# design.net
KiCad netlist of a schematic drawn in Altium Designer
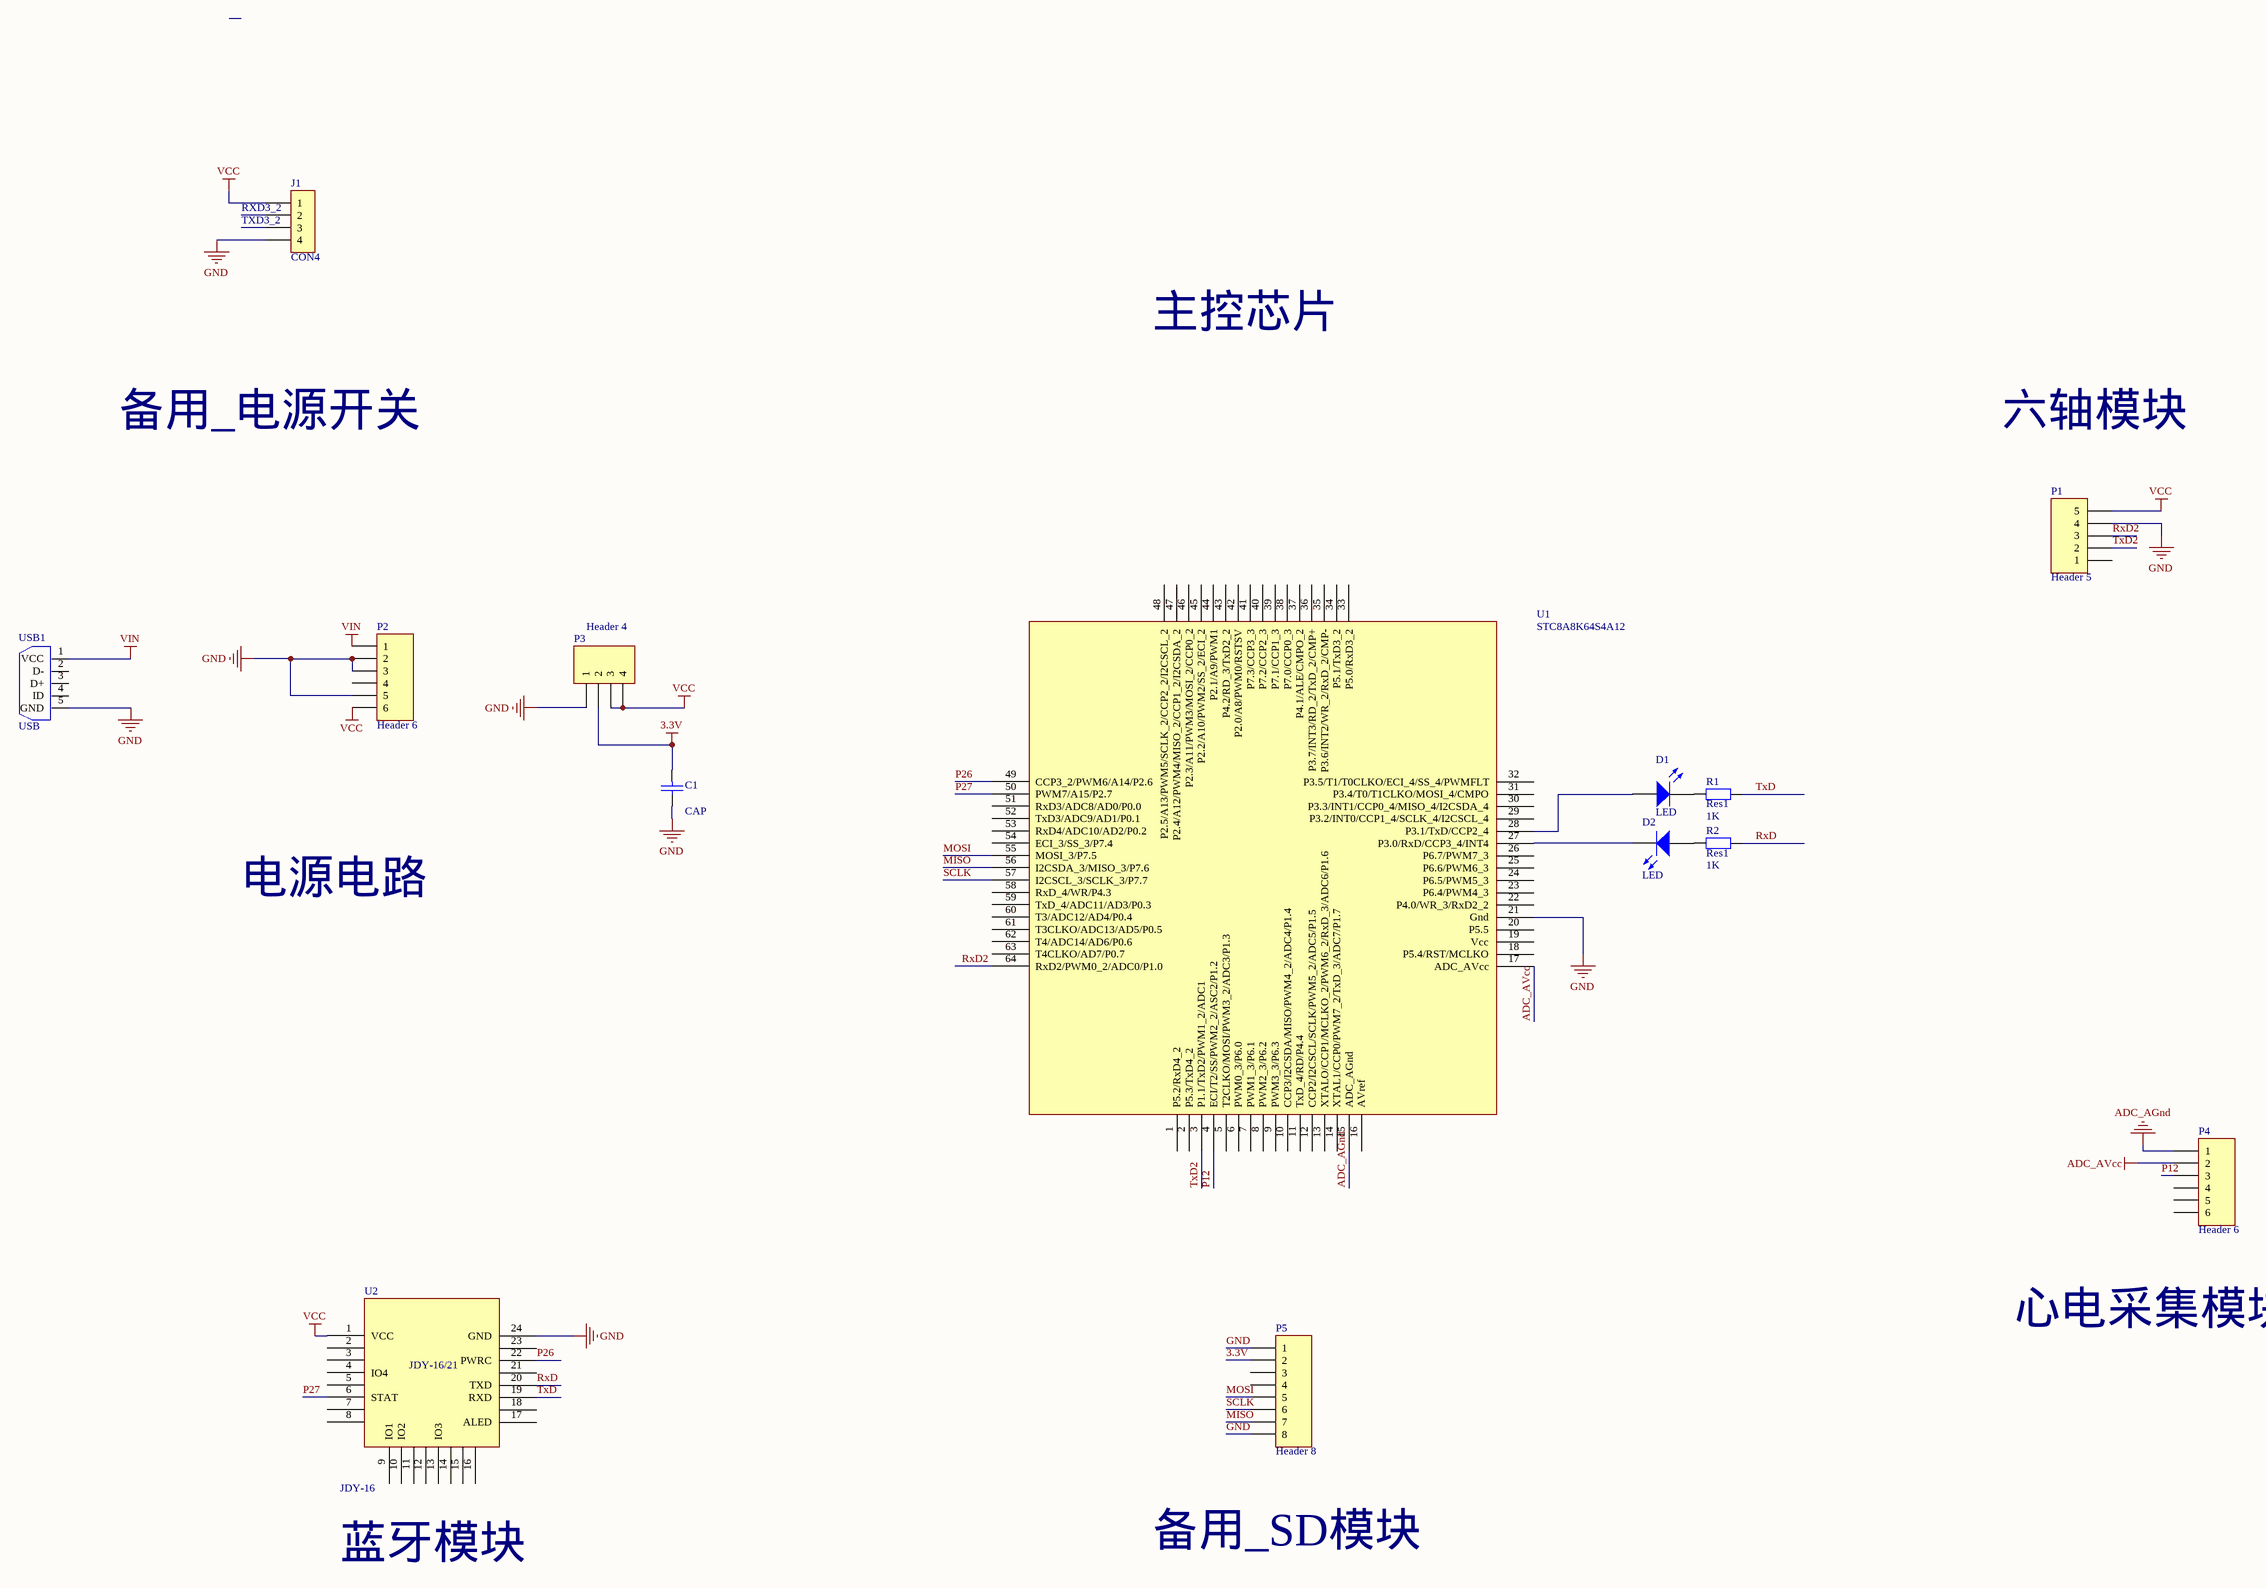
[diagram p0: 心电背心.SchDoc]

(export (version "E")
  (design (tool "Eeschema 10.0.6"))
  (components
    (comp (ref "C1")
      (value "CAP")
      (footprint "0805_L")
      (description "Capacitor")
      (libsource (lib "*") (part "CAP"))
    )
    (comp (ref "D1")
      (value "LED")
      (footprint "LED-0")
      (description "Typical INFRARED GaAs LED")
      (fields (field (name "PUBLISHER") "Altium Limited"))
      (libsource (lib "Miscellaneous Devices") (part "LED0"))
    )
    (comp (ref "D2")
      (value "LED")
      (footprint "LED-0")
      (description "Typical INFRARED GaAs LED")
      (fields (field (name "PUBLISHER") "Altium Limited"))
      (libsource (lib "Miscellaneous Devices") (part "LED0"))
    )
    (comp (ref "J1")
      (value "CON4")
      (footprint "SP4-1")
      (description "Connector")
      (libsource (lib "*") (part "CON4"))
    )
    (comp (ref "P1")
      (value "Header 5")
      (footprint "HDR1X5")
      (description "Header, 5-Pin")
      (fields (field (name "PUBLISHER") "Altium Limited"))
      (libsource (lib "Miscellaneous Connectors") (part "Header 5"))
    )
    (comp (ref "P2")
      (value "Header 6")
      (footprint "HT396K-6")
      (description "Header, 6-Pin")
      (fields (field (name "PUBLISHER") "Altium Limited"))
      (libsource (lib "01 Connect_IntegratedLibrary") (part "Header 6"))
    )
    (comp (ref "P3")
      (value "Header 4")
      (footprint "1117")
      (description "Header, 4-Pin")
      (fields (field (name "PUBLISHER") "Altium Limited"))
      (libsource (lib "Miscellaneous Connectors") (part "Header 4"))
    )
    (comp (ref "P4")
      (value "Header 6")
      (footprint "HT396K-6")
      (description "Header, 6-Pin")
      (fields (field (name "PUBLISHER") "Altium Limited"))
      (libsource (lib "01 Connect_IntegratedLibrary") (part "Header 6"))
    )
    (comp (ref "P5")
      (value "Header 8")
      (footprint "HDR1X8")
      (description "Header, 8-Pin")
      (fields (field (name "PUBLISHER") "Altium Limited"))
      (libsource (lib "03-EButterflyIntegratedLibrary") (part "Header 8"))
    )
    (comp (ref "R1")
      (value "Res1")
      (footprint "AXIAL-0.4")
      (description "Resistor")
      (fields (field (name "ALTIUM_VALUE") "1K") (field (name "PUBLISHER") "Altium Limited"))
      (libsource (lib "Miscellaneous Devices") (part "Res2"))
    )
    (comp (ref "R2")
      (value "Res1")
      (footprint "AXIAL-0.4")
      (description "Resistor")
      (fields (field (name "ALTIUM_VALUE") "1K") (field (name "PUBLISHER") "Altium Limited"))
      (libsource (lib "Miscellaneous Devices") (part "Res2"))
    )
    (comp (ref "U1")
      (value "STC8A8K64S4A12")
      (footprint "LQFP-64_10x10x05P_Q2")
      (description "LQFP64")
      (libsource (lib "02 Miscellaneous_Devices_ZSF_Library") (part "STC8A8K64S4A12"))
    )
    (comp (ref "U2") (value "JDY-16") (footprint "JDY16") (libsource (lib "stc64") (part "JDY21")))
    (comp (ref "USB1")
      (value "USB")
      (footprint "MICRO_USB5P_SOP")
      (libsource (lib "01 Connect_IntegratedLibrary") (part "USB5"))
    )
  )
  (nets
    (net (code "1") (name "/MISO") (class "Default")
      (node (ref "P5") (pin "7") (pinfunction "7_7") (pintype "passive"))
      (node (ref "U1") (pin "56") (pinfunction "I2CSDA_3/MISO_3/P7.6_56") (pintype "passive"))
    )
    (net (code "2") (name "/MOSI") (class "Default")
      (node (ref "P5") (pin "5") (pinfunction "5_5") (pintype "passive"))
      (node (ref "U1") (pin "55") (pinfunction "MOSI_3/P7.5_55") (pintype "passive"))
    )
    (net (code "3") (name "/P12") (class "Default")
      (node (ref "P4") (pin "3") (pinfunction "3_3") (pintype "passive"))
      (node (ref "U1") (pin "4") (pinfunction "ECI/T2/SS/PWM2_2/ASC2/P1.2_4") (pintype "passive"))
    )
    (net (code "4") (name "/P26") (class "Default")
      (node (ref "U1") (pin "49") (pinfunction "CCP3_2/PWM6/A14/P2.6_49") (pintype "passive"))
      (node (ref "U2") (pin "22") (pinfunction "PWRC_22") (pintype "passive"))
    )
    (net (code "5") (name "/P27") (class "Default")
      (node (ref "U1") (pin "50") (pinfunction "PWM7/A15/P2.7_50") (pintype "passive"))
      (node (ref "U2") (pin "6") (pinfunction "STAT_6") (pintype "passive"))
    )
    (net (code "6") (name "/RxD") (class "Default")
      (node (ref "R2") (pin "2") (pinfunction "2_2") (pintype "passive"))
      (node (ref "U2") (pin "20") (pinfunction "TXD_20") (pintype "passive"))
    )
    (net (code "7") (name "/RxD2") (class "Default")
      (node (ref "P1") (pin "3") (pinfunction "3_3") (pintype "passive"))
      (node (ref "U1") (pin "64") (pinfunction "RxD2/PWM0_2/ADC0/P1.0_64") (pintype "passive"))
    )
    (net (code "8") (name "/SCLK") (class "Default")
      (node (ref "P5") (pin "6") (pinfunction "6_6") (pintype "passive"))
      (node (ref "U1") (pin "57") (pinfunction "I2CSCL_3/SCLK_3/P7.7_57") (pintype "passive"))
    )
    (net (code "9") (name "/TxD") (class "Default")
      (node (ref "R1") (pin "2") (pinfunction "2_2") (pintype "passive"))
      (node (ref "U2") (pin "19") (pinfunction "RXD_19") (pintype "passive"))
    )
    (net (code "10") (name "/TxD2") (class "Default")
      (node (ref "P1") (pin "2") (pinfunction "2_2") (pintype "passive"))
      (node (ref "U1") (pin "3") (pinfunction "P1.1/TxD2/PWM1_2/ADC1_3") (pintype "passive"))
    )
    (net (code "11") (name "3.3V") (class "Default")
      (node (ref "C1") (pin "1") (pinfunction "1_1") (pintype "passive"))
      (node (ref "P3") (pin "2") (pinfunction "2_2") (pintype "passive"))
      (node (ref "P5") (pin "2") (pinfunction "2_2") (pintype "passive"))
    )
    (net (code "12") (name "ADC_AGnd") (class "Default")
      (node (ref "P4") (pin "1") (pinfunction "1_1") (pintype "passive"))
      (node (ref "U1") (pin "15") (pinfunction "ADC_AGnd_15") (pintype "passive"))
    )
    (net (code "13") (name "ADC_AVcc") (class "Default")
      (node (ref "P4") (pin "2") (pinfunction "2_2") (pintype "passive"))
      (node (ref "U1") (pin "17") (pinfunction "ADC_AVcc_17") (pintype "passive"))
    )
    (net (code "14") (name "GND") (class "Default")
      (node (ref "C1") (pin "2") (pinfunction "2_2") (pintype "passive"))
      (node (ref "J1") (pin "4") (pinfunction "4_4") (pintype "passive"))
      (node (ref "P1") (pin "4") (pinfunction "4_4") (pintype "passive"))
      (node (ref "P2") (pin "2") (pinfunction "2_2") (pintype "passive"))
      (node (ref "P2") (pin "3") (pinfunction "3_3") (pintype "passive"))
      (node (ref "P2") (pin "5") (pinfunction "5_5") (pintype "passive"))
      (node (ref "P3") (pin "1") (pinfunction "1_1") (pintype "passive"))
      (node (ref "P5") (pin "1") (pinfunction "1_1") (pintype "passive"))
      (node (ref "P5") (pin "8") (pinfunction "8_8") (pintype "passive"))
      (node (ref "U1") (pin "21") (pinfunction "Gnd_21") (pintype "passive"))
      (node (ref "U2") (pin "24") (pinfunction "GND_24") (pintype "passive"))
      (node (ref "USB1") (pin "5") (pinfunction "GND_5") (pintype "passive"))
    )
    (net (code "15") (name "Net-(D1-A)") (class "Default")
      (node (ref "D1") (pin "1") (pinfunction "A_1") (pintype "passive"))
      (node (ref "U1") (pin "28") (pinfunction "P3.1/TxD/CCP2_4_28") (pintype "passive"))
    )
    (net (code "16") (name "Net-(D1-K)") (class "Default")
      (node (ref "D1") (pin "2") (pinfunction "K_2") (pintype "passive"))
      (node (ref "R1") (pin "1") (pinfunction "1_1") (pintype "passive"))
    )
    (net (code "17") (name "Net-(D2-A)") (class "Default")
      (node (ref "D2") (pin "1") (pinfunction "A_1") (pintype "passive"))
      (node (ref "R2") (pin "1") (pinfunction "1_1") (pintype "passive"))
    )
    (net (code "18") (name "Net-(D2-K)") (class "Default")
      (node (ref "D2") (pin "2") (pinfunction "K_2") (pintype "passive"))
      (node (ref "U1") (pin "27") (pinfunction "P3.0/RxD/CCP3_4/INT4_27") (pintype "passive"))
    )
    (net (code "19") (name "VCC") (class "Default")
      (node (ref "J1") (pin "1") (pinfunction "1_1") (pintype "passive"))
      (node (ref "P1") (pin "5") (pinfunction "5_5") (pintype "passive"))
      (node (ref "P2") (pin "6") (pinfunction "6_6") (pintype "passive"))
      (node (ref "P3") (pin "3") (pinfunction "3_3") (pintype "passive"))
      (node (ref "P3") (pin "4") (pinfunction "4_4") (pintype "passive"))
      (node (ref "U2") (pin "1") (pinfunction "VCC_1") (pintype "passive"))
    )
    (net (code "20") (name "VIN") (class "Default")
      (node (ref "P2") (pin "1") (pinfunction "1_1") (pintype "passive"))
      (node (ref "USB1") (pin "1") (pinfunction "VCC_1") (pintype "passive"))
    )
    (net (code "21") (name "unconnected-(J1-Pad2)") (class "Default")
      (node (ref "J1") (pin "2") (pinfunction "2_2") (pintype "passive"))
    )
    (net (code "22") (name "unconnected-(J1-Pad3)") (class "Default")
      (node (ref "J1") (pin "3") (pinfunction "3_3") (pintype "passive"))
    )
    (net (code "23") (name "unconnected-(P1-Pad1)") (class "Default")
      (node (ref "P1") (pin "1") (pinfunction "1_1") (pintype "passive"))
    )
    (net (code "24") (name "unconnected-(P2-Pad4)") (class "Default")
      (node (ref "P2") (pin "4") (pinfunction "4_4") (pintype "passive"))
    )
    (net (code "25") (name "unconnected-(P4-Pad4)") (class "Default")
      (node (ref "P4") (pin "4") (pinfunction "4_4") (pintype "passive"))
    )
    (net (code "26") (name "unconnected-(P4-Pad5)") (class "Default")
      (node (ref "P4") (pin "5") (pinfunction "5_5") (pintype "passive"))
    )
    (net (code "27") (name "unconnected-(P4-Pad6)") (class "Default")
      (node (ref "P4") (pin "6") (pinfunction "6_6") (pintype "passive"))
    )
    (net (code "28") (name "unconnected-(P5-Pad3)") (class "Default")
      (node (ref "P5") (pin "3") (pinfunction "3_3") (pintype "passive"))
    )
    (net (code "29") (name "unconnected-(P5-Pad4)") (class "Default")
      (node (ref "P5") (pin "4") (pinfunction "4_4") (pintype "passive"))
    )
    (net (code "30") (name "unconnected-(U1-AVref-Pad16)") (class "Default")
      (node (ref "U1") (pin "16") (pinfunction "AVref_16") (pintype "passive"))
    )
    (net (code "31") (name "unconnected-(U1-CCP2{slash}I2CSCL{slash}SCLK{slash}PWM5_2{slash}ADC5{slash}P1.5-Pad12)") (class "Default")
      (node (ref "U1") (pin "12") (pinfunction "CCP2/I2CSCL/SCLK/PWM5_2/ADC5/P1.5_12") (pintype "passive"))
    )
    (net (code "32") (name "unconnected-(U1-CCP3{slash}I2CSDA{slash}MISO{slash}PWM4_2{slash}ADC4{slash}P1.4-Pad10)") (class "Default")
      (node (ref "U1") (pin "10") (pinfunction "CCP3/I2CSDA/MISO/PWM4_2/ADC4/P1.4_10") (pintype "passive"))
    )
    (net (code "33") (name "unconnected-(U1-ECI_3{slash}SS_3{slash}P7.4-Pad54)") (class "Default")
      (node (ref "U1") (pin "54") (pinfunction "ECI_3/SS_3/P7.4_54") (pintype "passive"))
    )
    (net (code "34") (name "unconnected-(U1-P2.0{slash}A8{slash}PWM0{slash}RSTSV-Pad42)") (class "Default")
      (node (ref "U1") (pin "42") (pinfunction "P2.0/A8/PWM0/RSTSV_42") (pintype "passive"))
    )
    (net (code "35") (name "unconnected-(U1-P2.1{slash}A9{slash}PWM1-Pad44)") (class "Default")
      (node (ref "U1") (pin "44") (pinfunction "P2.1/A9/PWM1_44") (pintype "passive"))
    )
    (net (code "36") (name "unconnected-(U1-P2.2{slash}A10{slash}PWM2{slash}SS_2{slash}ECI_2-Pad45)") (class "Default")
      (node (ref "U1") (pin "45") (pinfunction "P2.2/A10/PWM2/SS_2/ECI_2_45") (pintype "passive"))
    )
    (net (code "37") (name "unconnected-(U1-P2.3{slash}A11{slash}PWM3{slash}MOSI_2{slash}CCP0_2-Pad46)") (class "Default")
      (node (ref "U1") (pin "46") (pinfunction "P2.3/A11/PWM3/MOSI_2/CCP0_2_46") (pintype "passive"))
    )
    (net (code "38") (name "unconnected-(U1-P2.4{slash}A12{slash}PWM4{slash}MISO_2{slash}CCP1_2{slash}I2CSDA_2-Pad47)") (class "Default")
      (node (ref "U1") (pin "47") (pinfunction "P2.4/A12/PWM4/MISO_2/CCP1_2/I2CSDA_2_47") (pintype "passive"))
    )
    (net (code "39") (name "unconnected-(U1-P2.5{slash}A13{slash}PWM5{slash}SCLK_2{slash}CCP2_2{slash}I2CSCL_2-Pad48)") (class "Default")
      (node (ref "U1") (pin "48") (pinfunction "P2.5/A13/PWM5/SCLK_2/CCP2_2/I2CSCL_2_48") (pintype "passive"))
    )
    (net (code "40") (name "unconnected-(U1-P3.2{slash}INT0{slash}CCP1_4{slash}SCLK_4{slash}I2CSCL_4-Pad29)") (class "Default")
      (node (ref "U1") (pin "29") (pinfunction "P3.2/INT0/CCP1_4/SCLK_4/I2CSCL_4_29") (pintype "passive"))
    )
    (net (code "41") (name "unconnected-(U1-P3.3{slash}INT1{slash}CCP0_4{slash}MISO_4{slash}I2CSDA_4-Pad30)") (class "Default")
      (node (ref "U1") (pin "30") (pinfunction "P3.3/INT1/CCP0_4/MISO_4/I2CSDA_4_30") (pintype "passive"))
    )
    (net (code "42") (name "unconnected-(U1-P3.4{slash}T0{slash}T1CLKO{slash}MOSI_4{slash}CMPO-Pad31)") (class "Default")
      (node (ref "U1") (pin "31") (pinfunction "P3.4/T0/T1CLKO/MOSI_4/CMPO_31") (pintype "passive"))
    )
    (net (code "43") (name "unconnected-(U1-P3.5{slash}T1{slash}T0CLKO{slash}ECI_4{slash}SS_4{slash}PWMFLT-Pad32)") (class "Default")
      (node (ref "U1") (pin "32") (pinfunction "P3.5/T1/T0CLKO/ECI_4/SS_4/PWMFLT_32") (pintype "passive"))
    )
    (net (code "44") (name "unconnected-(U1-P3.6{slash}INT2{slash}WR_2{slash}RxD_2{slash}CMP--Pad35)") (class "Default")
      (node (ref "U1") (pin "35") (pinfunction "P3.6/INT2/WR_2/RxD_2/CMP-_35") (pintype "passive"))
    )
    (net (code "45") (name "unconnected-(U1-P3.7{slash}INT3{slash}RD_2{slash}TxD_2{slash}CMP+-Pad36)") (class "Default")
      (node (ref "U1") (pin "36") (pinfunction "P3.7/INT3/RD_2/TxD_2/CMP+_36") (pintype "passive"))
    )
    (net (code "46") (name "unconnected-(U1-P4.0{slash}WR_3{slash}RxD2_2-Pad22)") (class "Default")
      (node (ref "U1") (pin "22") (pinfunction "P4.0/WR_3/RxD2_2_22") (pintype "passive"))
    )
    (net (code "47") (name "unconnected-(U1-P4.1{slash}ALE{slash}CMPO_2-Pad37)") (class "Default")
      (node (ref "U1") (pin "37") (pinfunction "P4.1/ALE/CMPO_2_37") (pintype "passive"))
    )
    (net (code "48") (name "unconnected-(U1-P4.2{slash}RD_3{slash}TxD2_2-Pad43)") (class "Default")
      (node (ref "U1") (pin "43") (pinfunction "P4.2/RD_3/TxD2_2_43") (pintype "passive"))
    )
    (net (code "49") (name "unconnected-(U1-P5.0{slash}RxD3_2-Pad33)") (class "Default")
      (node (ref "U1") (pin "33") (pinfunction "P5.0/RxD3_2_33") (pintype "passive"))
    )
    (net (code "50") (name "unconnected-(U1-P5.1{slash}TxD3_2-Pad34)") (class "Default")
      (node (ref "U1") (pin "34") (pinfunction "P5.1/TxD3_2_34") (pintype "passive"))
    )
    (net (code "51") (name "unconnected-(U1-P5.2{slash}RxD4_2-Pad1)") (class "Default")
      (node (ref "U1") (pin "1") (pinfunction "P5.2/RxD4_2_1") (pintype "passive"))
    )
    (net (code "52") (name "unconnected-(U1-P5.3{slash}TxD4_2-Pad2)") (class "Default")
      (node (ref "U1") (pin "2") (pinfunction "P5.3/TxD4_2_2") (pintype "passive"))
    )
    (net (code "53") (name "unconnected-(U1-P5.4{slash}RST{slash}MCLKO-Pad18)") (class "Default")
      (node (ref "U1") (pin "18") (pinfunction "P5.4/RST/MCLKO_18") (pintype "passive"))
    )
    (net (code "54") (name "unconnected-(U1-P5.5-Pad20)") (class "Default")
      (node (ref "U1") (pin "20") (pinfunction "P5.5_20") (pintype "passive"))
    )
    (net (code "55") (name "unconnected-(U1-P6.4{slash}PWM4_3-Pad23)") (class "Default")
      (node (ref "U1") (pin "23") (pinfunction "P6.4/PWM4_3_23") (pintype "passive"))
    )
    (net (code "56") (name "unconnected-(U1-P6.5{slash}PWM5_3-Pad24)") (class "Default")
      (node (ref "U1") (pin "24") (pinfunction "P6.5/PWM5_3_24") (pintype "passive"))
    )
    (net (code "57") (name "unconnected-(U1-P6.6{slash}PWM6_3-Pad25)") (class "Default")
      (node (ref "U1") (pin "25") (pinfunction "P6.6/PWM6_3_25") (pintype "passive"))
    )
    (net (code "58") (name "unconnected-(U1-P6.7{slash}PWM7_3-Pad26)") (class "Default")
      (node (ref "U1") (pin "26") (pinfunction "P6.7/PWM7_3_26") (pintype "passive"))
    )
    (net (code "59") (name "unconnected-(U1-P7.0{slash}CCP0_3-Pad38)") (class "Default")
      (node (ref "U1") (pin "38") (pinfunction "P7.0/CCP0_3_38") (pintype "passive"))
    )
    (net (code "60") (name "unconnected-(U1-P7.1{slash}CCP1_3-Pad39)") (class "Default")
      (node (ref "U1") (pin "39") (pinfunction "P7.1/CCP1_3_39") (pintype "passive"))
    )
    (net (code "61") (name "unconnected-(U1-P7.2{slash}CCP2_3-Pad40)") (class "Default")
      (node (ref "U1") (pin "40") (pinfunction "P7.2/CCP2_3_40") (pintype "passive"))
    )
    (net (code "62") (name "unconnected-(U1-P7.3{slash}CCP3_3-Pad41)") (class "Default")
      (node (ref "U1") (pin "41") (pinfunction "P7.3/CCP3_3_41") (pintype "passive"))
    )
    (net (code "63") (name "unconnected-(U1-PWM0_3{slash}P6.0-Pad6)") (class "Default")
      (node (ref "U1") (pin "6") (pinfunction "PWM0_3/P6.0_6") (pintype "passive"))
    )
    (net (code "64") (name "unconnected-(U1-PWM1_3{slash}P6.1-Pad7)") (class "Default")
      (node (ref "U1") (pin "7") (pinfunction "PWM1_3/P6.1_7") (pintype "passive"))
    )
    (net (code "65") (name "unconnected-(U1-PWM2_3{slash}P6.2-Pad8)") (class "Default")
      (node (ref "U1") (pin "8") (pinfunction "PWM2_3/P6.2_8") (pintype "passive"))
    )
    (net (code "66") (name "unconnected-(U1-PWM3_3{slash}P6.3-Pad9)") (class "Default")
      (node (ref "U1") (pin "9") (pinfunction "PWM3_3/P6.3_9") (pintype "passive"))
    )
    (net (code "67") (name "unconnected-(U1-RxD3{slash}ADC8{slash}AD0{slash}P0.0-Pad51)") (class "Default")
      (node (ref "U1") (pin "51") (pinfunction "RxD3/ADC8/AD0/P0.0_51") (pintype "passive"))
    )
    (net (code "68") (name "unconnected-(U1-RxD4{slash}ADC10{slash}AD2{slash}P0.2-Pad53)") (class "Default")
      (node (ref "U1") (pin "53") (pinfunction "RxD4/ADC10/AD2/P0.2_53") (pintype "passive"))
    )
    (net (code "69") (name "unconnected-(U1-RxD_4{slash}WR{slash}P4.3-Pad58)") (class "Default")
      (node (ref "U1") (pin "58") (pinfunction "RxD_4/WR/P4.3_58") (pintype "passive"))
    )
    (net (code "70") (name "unconnected-(U1-T2CLKO{slash}MOSI{slash}PWM3_2{slash}ADC3{slash}P1.3-Pad5)") (class "Default")
      (node (ref "U1") (pin "5") (pinfunction "T2CLKO/MOSI/PWM3_2/ADC3/P1.3_5") (pintype "passive"))
    )
    (net (code "71") (name "unconnected-(U1-T3CLKO{slash}ADC13{slash}AD5{slash}P0.5-Pad61)") (class "Default")
      (node (ref "U1") (pin "61") (pinfunction "T3CLKO/ADC13/AD5/P0.5_61") (pintype "passive"))
    )
    (net (code "72") (name "unconnected-(U1-T3{slash}ADC12{slash}AD4{slash}P0.4-Pad60)") (class "Default")
      (node (ref "U1") (pin "60") (pinfunction "T3/ADC12/AD4/P0.4_60") (pintype "passive"))
    )
    (net (code "73") (name "unconnected-(U1-T4CLKO{slash}AD7{slash}P0.7-Pad63)") (class "Default")
      (node (ref "U1") (pin "63") (pinfunction "T4CLKO/AD7/P0.7_63") (pintype "passive"))
    )
    (net (code "74") (name "unconnected-(U1-T4{slash}ADC14{slash}AD6{slash}P0.6-Pad62)") (class "Default")
      (node (ref "U1") (pin "62") (pinfunction "T4/ADC14/AD6/P0.6_62") (pintype "passive"))
    )
    (net (code "75") (name "unconnected-(U1-TxD3{slash}ADC9{slash}AD1{slash}P0.1-Pad52)") (class "Default")
      (node (ref "U1") (pin "52") (pinfunction "TxD3/ADC9/AD1/P0.1_52") (pintype "passive"))
    )
    (net (code "76") (name "unconnected-(U1-TxD_4{slash}ADC11{slash}AD3{slash}P0.3-Pad59)") (class "Default")
      (node (ref "U1") (pin "59") (pinfunction "TxD_4/ADC11/AD3/P0.3_59") (pintype "passive"))
    )
    (net (code "77") (name "unconnected-(U1-TxD_4{slash}RD{slash}P4.4-Pad11)") (class "Default")
      (node (ref "U1") (pin "11") (pinfunction "TxD_4/RD/P4.4_11") (pintype "passive"))
    )
    (net (code "78") (name "unconnected-(U1-Vcc-Pad19)") (class "Default")
      (node (ref "U1") (pin "19") (pinfunction "Vcc_19") (pintype "passive"))
    )
    (net (code "79") (name "unconnected-(U1-XTAL1{slash}CCP0{slash}PWM7_2{slash}TxD_3{slash}ADC7{slash}P1.7-Pad14)") (class "Default")
      (node (ref "U1") (pin "14") (pinfunction "XTAL1/CCP0/PWM7_2/TxD_3/ADC7/P1.7_14") (pintype "passive"))
    )
    (net (code "80") (name "unconnected-(U1-XTALO{slash}CCP1{slash}MCLKO_2{slash}PWM6_2{slash}RxD_3{slash}ADC6{slash}P1.6-Pad13)") (class "Default")
      (node (ref "U1") (pin "13") (pinfunction "XTALO/CCP1/MCLKO_2/PWM6_2/RxD_3/ADC6/P1.6_13") (pintype "passive"))
    )
    (net (code "81") (name "unconnected-(U2-ALED-Pad17)") (class "Default")
      (node (ref "U2") (pin "17") (pinfunction "ALED_17") (pintype "passive"))
    )
    (net (code "82") (name "unconnected-(U2-IO1-Pad9)") (class "Default")
      (node (ref "U2") (pin "9") (pinfunction "IO1_9") (pintype "passive"))
    )
    (net (code "83") (name "unconnected-(U2-IO2-Pad10)") (class "Default")
      (node (ref "U2") (pin "10") (pinfunction "IO2_10") (pintype "passive"))
    )
    (net (code "84") (name "unconnected-(U2-IO3-Pad13)") (class "Default")
      (node (ref "U2") (pin "13") (pinfunction "IO3_13") (pintype "passive"))
    )
    (net (code "85") (name "unconnected-(U2-IO4-Pad4)") (class "Default")
      (node (ref "U2") (pin "4") (pinfunction "IO4_4") (pintype "passive"))
    )
    (net (code "86") (name "unconnected-(U2-Pad2)") (class "Default")
      (node (ref "U2") (pin "2") (pintype "passive"))
    )
    (net (code "87") (name "unconnected-(U2-Pad3)") (class "Default")
      (node (ref "U2") (pin "3") (pintype "passive"))
    )
    (net (code "88") (name "unconnected-(U2-Pad5)") (class "Default")
      (node (ref "U2") (pin "5") (pintype "passive"))
    )
    (net (code "89") (name "unconnected-(U2-Pad7)") (class "Default")
      (node (ref "U2") (pin "7") (pintype "passive"))
    )
    (net (code "90") (name "unconnected-(U2-Pad8)") (class "Default")
      (node (ref "U2") (pin "8") (pintype "passive"))
    )
    (net (code "91") (name "unconnected-(U2-Pad11)") (class "Default")
      (node (ref "U2") (pin "11") (pintype "passive"))
    )
    (net (code "92") (name "unconnected-(U2-Pad12)") (class "Default")
      (node (ref "U2") (pin "12") (pintype "passive"))
    )
    (net (code "93") (name "unconnected-(U2-Pad14)") (class "Default")
      (node (ref "U2") (pin "14") (pintype "passive"))
    )
    (net (code "94") (name "unconnected-(U2-Pad15)") (class "Default")
      (node (ref "U2") (pin "15") (pintype "passive"))
    )
    (net (code "95") (name "unconnected-(U2-Pad16)") (class "Default")
      (node (ref "U2") (pin "16") (pintype "passive"))
    )
    (net (code "96") (name "unconnected-(U2-Pad18)") (class "Default")
      (node (ref "U2") (pin "18") (pintype "passive"))
    )
    (net (code "97") (name "unconnected-(U2-Pad21)") (class "Default")
      (node (ref "U2") (pin "21") (pintype "passive"))
    )
    (net (code "98") (name "unconnected-(U2-Pad23)") (class "Default")
      (node (ref "U2") (pin "23") (pintype "passive"))
    )
    (net (code "99") (name "unconnected-(USB1-D+-Pad3)") (class "Default")
      (node (ref "USB1") (pin "3") (pinfunction "D+_3") (pintype "passive"))
    )
    (net (code "100") (name "unconnected-(USB1-D--Pad2)") (class "Default")
      (node (ref "USB1") (pin "2") (pinfunction "D-_2") (pintype "passive"))
    )
    (net (code "101") (name "unconnected-(USB1-ID-Pad4)") (class "Default")
      (node (ref "USB1") (pin "4") (pinfunction "ID_4") (pintype "passive"))
    )
  )
)
